# Solenoid_Driver.net
KiCad netlist of a schematic drawn in EAGLE
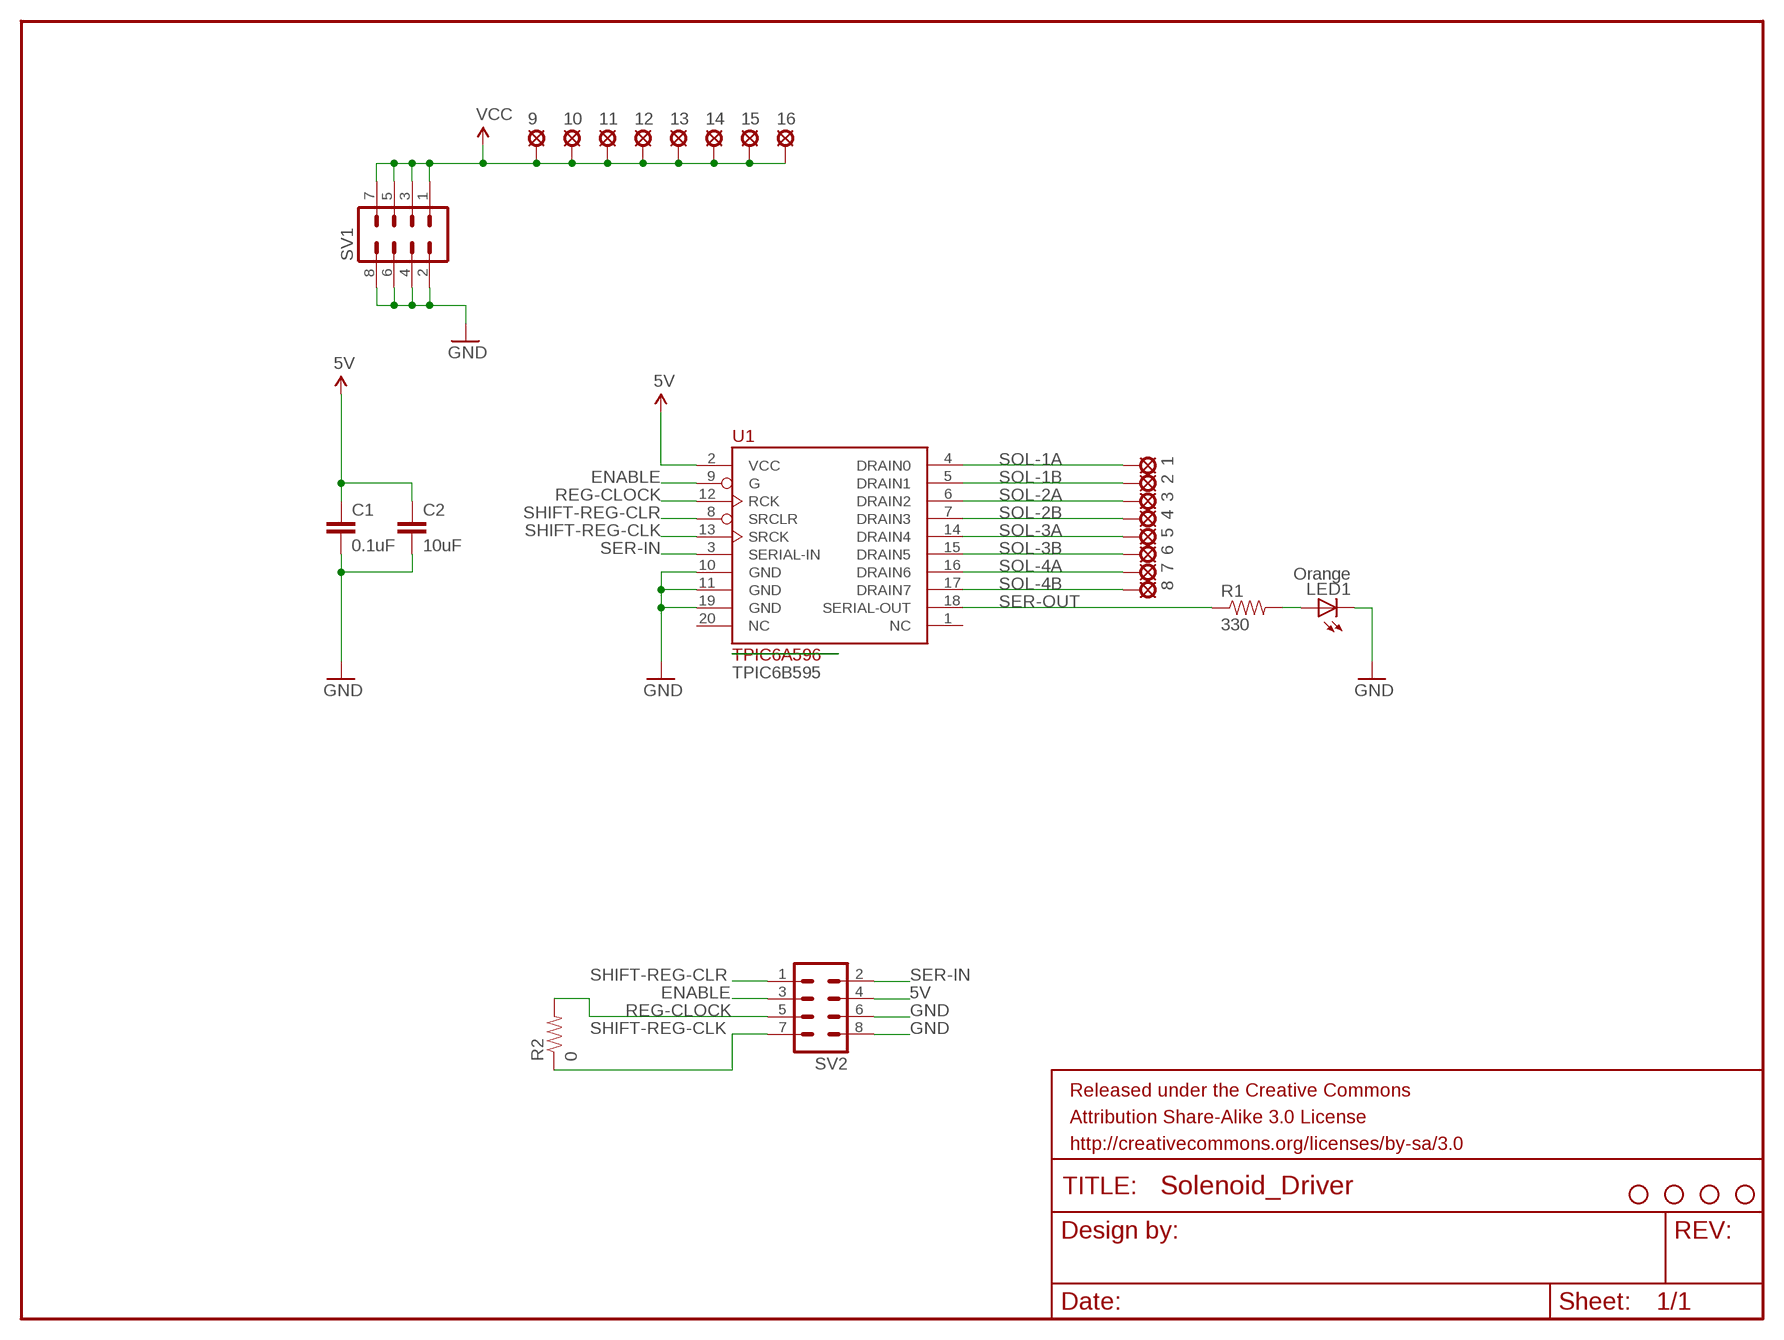
[diagram p0: schematic, sheet 1]

(export (version "E")
  (design (tool "Eeschema 10.0.6"))
  (components
    (comp (ref "1")
      (value "SE14")
      (footprint "eagle-import:SE14")
      (libsource (lib "eagle-import") (part "SE14"))
    )
    (comp (ref "2")
      (value "SE14")
      (footprint "eagle-import:SE14")
      (libsource (lib "eagle-import") (part "SE14"))
    )
    (comp (ref "3")
      (value "SE14")
      (footprint "eagle-import:SE14")
      (libsource (lib "eagle-import") (part "SE14"))
    )
    (comp (ref "4")
      (value "SE14")
      (footprint "eagle-import:SE14")
      (libsource (lib "eagle-import") (part "SE14"))
    )
    (comp (ref "5")
      (value "SE14")
      (footprint "eagle-import:SE14")
      (libsource (lib "eagle-import") (part "SE14"))
    )
    (comp (ref "6")
      (value "SE14")
      (footprint "eagle-import:SE14")
      (libsource (lib "eagle-import") (part "SE14"))
    )
    (comp (ref "7")
      (value "SE14")
      (footprint "eagle-import:SE14")
      (libsource (lib "eagle-import") (part "SE14"))
    )
    (comp (ref "8")
      (value "SE14")
      (footprint "eagle-import:SE14")
      (libsource (lib "eagle-import") (part "SE14"))
    )
    (comp (ref "9")
      (value "SE14")
      (footprint "eagle-import:SE14")
      (libsource (lib "eagle-import") (part "SE14"))
    )
    (comp (ref "10")
      (value "SE14")
      (footprint "eagle-import:SE14")
      (libsource (lib "eagle-import") (part "SE14"))
    )
    (comp (ref "11")
      (value "SE14")
      (footprint "eagle-import:SE14")
      (libsource (lib "eagle-import") (part "SE14"))
    )
    (comp (ref "12")
      (value "SE14")
      (footprint "eagle-import:SE14")
      (libsource (lib "eagle-import") (part "SE14"))
    )
    (comp (ref "13")
      (value "SE14")
      (footprint "eagle-import:SE14")
      (libsource (lib "eagle-import") (part "SE14"))
    )
    (comp (ref "14")
      (value "SE14")
      (footprint "eagle-import:SE14")
      (libsource (lib "eagle-import") (part "SE14"))
    )
    (comp (ref "15")
      (value "SE14")
      (footprint "eagle-import:SE14")
      (libsource (lib "eagle-import") (part "SE14"))
    )
    (comp (ref "16")
      (value "SE14")
      (footprint "eagle-import:SE14")
      (libsource (lib "eagle-import") (part "SE14"))
    )
    (comp (ref "C1")
      (value "0.1uF")
      (footprint "eagle-import:0603-CAP")
      (libsource (lib "eagle-import") (part "CAP0603-CAP"))
    )
    (comp (ref "C2")
      (value "10uF")
      (footprint "eagle-import:0603-CAP")
      (libsource (lib "eagle-import") (part "CAP0603-CAP"))
    )
    (comp (ref "JP1")
      (value "STAND-OFF")
      (footprint "eagle-import:STAND-OFF")
      (libsource (lib "eagle-import") (part "STAND-OFF"))
    )
    (comp (ref "JP2")
      (value "STAND-OFF")
      (footprint "eagle-import:STAND-OFF")
      (libsource (lib "eagle-import") (part "STAND-OFF"))
    )
    (comp (ref "JP3")
      (value "STAND-OFF")
      (footprint "eagle-import:STAND-OFF")
      (libsource (lib "eagle-import") (part "STAND-OFF"))
    )
    (comp (ref "JP4")
      (value "STAND-OFF")
      (footprint "eagle-import:STAND-OFF")
      (libsource (lib "eagle-import") (part "STAND-OFF"))
    )
    (comp (ref "LED1")
      (value "Orange")
      (footprint "eagle-import:LED-0603")
      (libsource (lib "eagle-import") (part "LED0603"))
    )
    (comp (ref "R1")
      (value "330")
      (footprint "eagle-import:0603-RES")
      (libsource (lib "eagle-import") (part "RESISTOR0603-RES"))
    )
    (comp (ref "R2")
      (value "0")
      (footprint "eagle-import:0603-RES")
      (libsource (lib "eagle-import") (part "RESISTOR0603-RES"))
    )
    (comp (ref "SV1")
      (value "MA04-2")
      (footprint "eagle-import:MA04-2")
      (libsource (lib "eagle-import") (part "MA04-2"))
    )
    (comp (ref "SV2")
      (value "MA04-2")
      (footprint "eagle-import:MA04-2")
      (libsource (lib "eagle-import") (part "MA04-2"))
    )
    (comp (ref "U1")
      (value "TPIC6A596")
      (footprint "eagle-import:SOIC20-W")
      (libsource (lib "eagle-import") (part "TPIC6A596"))
    )
  )
  (nets
    (net (code "1") (name "/ENABLE") (class "Default")
      (node (ref "SV2") (pin "3") (pinfunction "3_3") (pintype "passive"))
      (node (ref "U1") (pin "9") (pinfunction "G_9") (pintype "bidirectional"))
    )
    (net (code "2") (name "/REG-CLOCK") (class "Default")
      (node (ref "R2") (pin "2") (pinfunction "2_2") (pintype "passive"))
      (node (ref "SV2") (pin "5") (pinfunction "5_5") (pintype "passive"))
      (node (ref "U1") (pin "12") (pinfunction "RCK_12") (pintype "bidirectional"))
    )
    (net (code "3") (name "/SER-IN") (class "Default")
      (node (ref "SV2") (pin "2") (pinfunction "2_2") (pintype "passive"))
      (node (ref "U1") (pin "3") (pinfunction "SERIAL-IN_3") (pintype "bidirectional"))
    )
    (net (code "4") (name "/SER-OUT") (class "Default")
      (node (ref "R1") (pin "1") (pinfunction "1_1") (pintype "passive"))
      (node (ref "U1") (pin "18") (pinfunction "SERIAL-OUT_18") (pintype "bidirectional"))
    )
    (net (code "5") (name "/SHIFT-REG-CLK") (class "Default")
      (node (ref "R2") (pin "1") (pinfunction "1_1") (pintype "passive"))
      (node (ref "SV2") (pin "7") (pinfunction "7_7") (pintype "passive"))
      (node (ref "U1") (pin "13") (pinfunction "SRCK_13") (pintype "bidirectional"))
    )
    (net (code "6") (name "/SHIFT-REG-CLR") (class "Default")
      (node (ref "SV2") (pin "1") (pinfunction "1_1") (pintype "passive"))
      (node (ref "U1") (pin "8") (pinfunction "SRCLR_8") (pintype "bidirectional"))
    )
    (net (code "7") (name "/SOL-1A") (class "Default")
      (node (ref "1") (pin "MP") (pinfunction "MP_MP") (pintype "passive"))
      (node (ref "U1") (pin "4") (pinfunction "DRAIN0_4") (pintype "bidirectional"))
    )
    (net (code "8") (name "/SOL-1B") (class "Default")
      (node (ref "2") (pin "MP") (pinfunction "MP_MP") (pintype "passive"))
      (node (ref "U1") (pin "5") (pinfunction "DRAIN1_5") (pintype "bidirectional"))
    )
    (net (code "9") (name "/SOL-2A") (class "Default")
      (node (ref "3") (pin "MP") (pinfunction "MP_MP") (pintype "passive"))
      (node (ref "U1") (pin "6") (pinfunction "DRAIN2_6") (pintype "bidirectional"))
    )
    (net (code "10") (name "/SOL-2B") (class "Default")
      (node (ref "4") (pin "MP") (pinfunction "MP_MP") (pintype "passive"))
      (node (ref "U1") (pin "7") (pinfunction "DRAIN3_7") (pintype "bidirectional"))
    )
    (net (code "11") (name "/SOL-3A") (class "Default")
      (node (ref "5") (pin "MP") (pinfunction "MP_MP") (pintype "passive"))
      (node (ref "U1") (pin "14") (pinfunction "DRAIN4_14") (pintype "bidirectional"))
    )
    (net (code "12") (name "/SOL-3B") (class "Default")
      (node (ref "6") (pin "MP") (pinfunction "MP_MP") (pintype "passive"))
      (node (ref "U1") (pin "15") (pinfunction "DRAIN5_15") (pintype "bidirectional"))
    )
    (net (code "13") (name "/SOL-4A") (class "Default")
      (node (ref "7") (pin "MP") (pinfunction "MP_MP") (pintype "passive"))
      (node (ref "U1") (pin "16") (pinfunction "DRAIN6_16") (pintype "bidirectional"))
    )
    (net (code "14") (name "/SOL-4B") (class "Default")
      (node (ref "8") (pin "MP") (pinfunction "MP_MP") (pintype "passive"))
      (node (ref "U1") (pin "17") (pinfunction "DRAIN7_17") (pintype "bidirectional"))
    )
    (net (code "15") (name "5V") (class "Default")
      (node (ref "C1") (pin "1") (pinfunction "1_1") (pintype "passive"))
      (node (ref "C2") (pin "1") (pinfunction "1_1") (pintype "passive"))
      (node (ref "SV2") (pin "4") (pinfunction "4_4") (pintype "passive"))
      (node (ref "U1") (pin "2") (pinfunction "VCC_2") (pintype "bidirectional"))
    )
    (net (code "16") (name "GND") (class "Default")
      (node (ref "C1") (pin "2") (pinfunction "2_2") (pintype "passive"))
      (node (ref "C2") (pin "2") (pinfunction "2_2") (pintype "passive"))
      (node (ref "LED1") (pin "C") (pinfunction "C_C") (pintype "passive"))
      (node (ref "SV1") (pin "2") (pinfunction "2_2") (pintype "passive"))
      (node (ref "SV1") (pin "4") (pinfunction "4_4") (pintype "passive"))
      (node (ref "SV1") (pin "6") (pinfunction "6_6") (pintype "passive"))
      (node (ref "SV1") (pin "8") (pinfunction "8_8") (pintype "passive"))
      (node (ref "SV2") (pin "6") (pinfunction "6_6") (pintype "passive"))
      (node (ref "SV2") (pin "8") (pinfunction "8_8") (pintype "passive"))
      (node (ref "U1") (pin "10") (pinfunction "GND_10") (pintype "bidirectional"))
      (node (ref "U1") (pin "11") (pinfunction "GND_11") (pintype "bidirectional"))
      (node (ref "U1") (pin "19") (pinfunction "GND_19") (pintype "bidirectional"))
    )
    (net (code "17") (name "Net-(LED1-PadA)") (class "Default")
      (node (ref "LED1") (pin "A") (pinfunction "A_A") (pintype "passive"))
      (node (ref "R1") (pin "2") (pinfunction "2_2") (pintype "passive"))
    )
    (net (code "18") (name "VCC") (class "Default")
      (node (ref "10") (pin "MP") (pinfunction "MP_MP") (pintype "passive"))
      (node (ref "11") (pin "MP") (pinfunction "MP_MP") (pintype "passive"))
      (node (ref "12") (pin "MP") (pinfunction "MP_MP") (pintype "passive"))
      (node (ref "13") (pin "MP") (pinfunction "MP_MP") (pintype "passive"))
      (node (ref "14") (pin "MP") (pinfunction "MP_MP") (pintype "passive"))
      (node (ref "15") (pin "MP") (pinfunction "MP_MP") (pintype "passive"))
      (node (ref "16") (pin "MP") (pinfunction "MP_MP") (pintype "passive"))
      (node (ref "9") (pin "MP") (pinfunction "MP_MP") (pintype "passive"))
      (node (ref "SV1") (pin "1") (pinfunction "1_1") (pintype "passive"))
      (node (ref "SV1") (pin "3") (pinfunction "3_3") (pintype "passive"))
      (node (ref "SV1") (pin "5") (pinfunction "5_5") (pintype "passive"))
      (node (ref "SV1") (pin "7") (pinfunction "7_7") (pintype "passive"))
    )
    (net (code "19") (name "unconnected-(U1-NC-Pad1)") (class "Default")
      (node (ref "U1") (pin "1") (pinfunction "NC_1") (pintype "bidirectional"))
    )
    (net (code "20") (name "unconnected-(U1-NC-Pad20)") (class "Default")
      (node (ref "U1") (pin "20") (pinfunction "NC_20") (pintype "bidirectional"))
    )
  )
)
